# MCU.net
KiCad netlist of a schematic drawn in Altium Designer
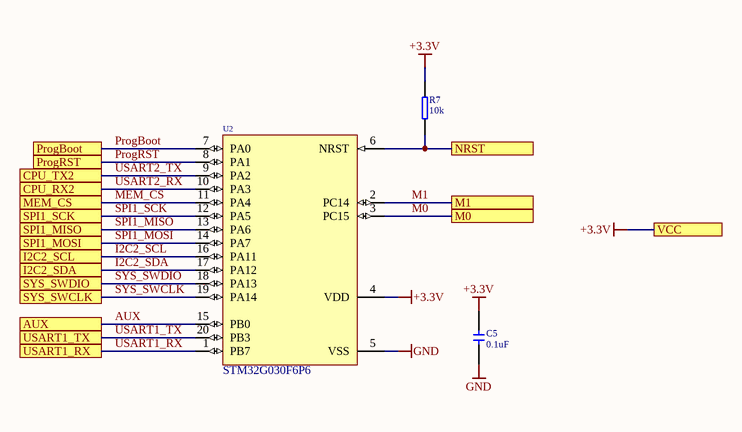
[diagram p0: MCU.SchDoc]

(export (version "E")
  (design (tool "Eeschema 10.0.6"))
  (components
    (comp (ref "C5")
      (value "0.1uF")
      (footprint "CERCAP 0402")
      (description "Capacitor")
      (fields (field (name "Comment") "CERCAP 0402 0.1uF * X7R"))
      (libsource (lib "!main") (part "!Capacitor"))
    )
    (comp (ref "R7")
      (value "10k")
      (footprint "RES 0402")
      (description "Resistor")
      (fields (field (name "Comment") "RES 0402 10k"))
      (libsource (lib "!main") (part "!Resistor"))
    )
    (comp (ref "U2")
      (value "STM32G030F6P6")
      (footprint "TSSOP-20")
      (description "Cortex-M0+")
      (libsource (lib "MCU_CPU") (part "STM32G030F6P6"))
    )
  )
  (nets
    (net (code "1") (name "+3.3V") (class "Default")
      (node (ref "C5") (pin "2") (pintype "passive"))
      (node (ref "R7") (pin "2") (pinfunction "12_2") (pintype "passive"))
      (node (ref "U2") (pin "4") (pinfunction "VDD_4") (pintype "power_in"))
    )
    (net (code "2") (name "/AUX") (class "Default")
      (node (ref "U2") (pin "15") (pinfunction "PB0_15") (pintype "bidirectional"))
    )
    (net (code "3") (name "/I2C2_SCL") (class "Default")
      (node (ref "U2") (pin "16") (pinfunction "PA11_16") (pintype "bidirectional"))
    )
    (net (code "4") (name "/I2C2_SDA") (class "Default")
      (node (ref "U2") (pin "17") (pinfunction "PA12_17") (pintype "bidirectional"))
    )
    (net (code "5") (name "/M0") (class "Default")
      (node (ref "U2") (pin "3") (pinfunction "PC15_3") (pintype "bidirectional"))
    )
    (net (code "6") (name "/M1") (class "Default")
      (node (ref "U2") (pin "2") (pinfunction "PC14_2") (pintype "bidirectional"))
    )
    (net (code "7") (name "/MEM_CS") (class "Default")
      (node (ref "U2") (pin "11") (pinfunction "PA4_11") (pintype "bidirectional"))
    )
    (net (code "8") (name "/NRST") (class "Default")
      (node (ref "R7") (pin "1") (pinfunction "11_1") (pintype "passive"))
      (node (ref "U2") (pin "6") (pinfunction "NRST_6") (pintype "input"))
    )
    (net (code "9") (name "/ProgBoot") (class "Default")
      (node (ref "U2") (pin "7") (pinfunction "PA0_7") (pintype "bidirectional"))
    )
    (net (code "10") (name "/ProgRST") (class "Default")
      (node (ref "U2") (pin "8") (pinfunction "PA1_8") (pintype "bidirectional"))
    )
    (net (code "11") (name "/SPI1_MISO") (class "Default")
      (node (ref "U2") (pin "13") (pinfunction "PA6_13") (pintype "bidirectional"))
    )
    (net (code "12") (name "/SPI1_MOSI") (class "Default")
      (node (ref "U2") (pin "14") (pinfunction "PA7_14") (pintype "bidirectional"))
    )
    (net (code "13") (name "/SPI1_SCK") (class "Default")
      (node (ref "U2") (pin "12") (pinfunction "PA5_12") (pintype "bidirectional"))
    )
    (net (code "14") (name "/SYS_SWCLK") (class "Default")
      (node (ref "U2") (pin "19") (pinfunction "PA14_19") (pintype "bidirectional"))
    )
    (net (code "15") (name "/SYS_SWDIO") (class "Default")
      (node (ref "U2") (pin "18") (pinfunction "PA13_18") (pintype "bidirectional"))
    )
    (net (code "16") (name "/USART1_RX") (class "Default")
      (node (ref "U2") (pin "1") (pinfunction "PB7_1") (pintype "bidirectional"))
    )
    (net (code "17") (name "/USART1_TX") (class "Default")
      (node (ref "U2") (pin "20") (pinfunction "PB3_20") (pintype "bidirectional"))
    )
    (net (code "18") (name "/USART2_RX") (class "Default")
      (node (ref "U2") (pin "10") (pinfunction "PA3_10") (pintype "bidirectional"))
    )
    (net (code "19") (name "/USART2_TX") (class "Default")
      (node (ref "U2") (pin "9") (pinfunction "PA2_9") (pintype "bidirectional"))
    )
    (net (code "20") (name "GND") (class "Default")
      (node (ref "C5") (pin "1") (pintype "passive"))
      (node (ref "U2") (pin "5") (pinfunction "VSS_5") (pintype "power_in"))
    )
  )
)
